# Sheet1.net
KiCad netlist of a schematic drawn in Altium Designer
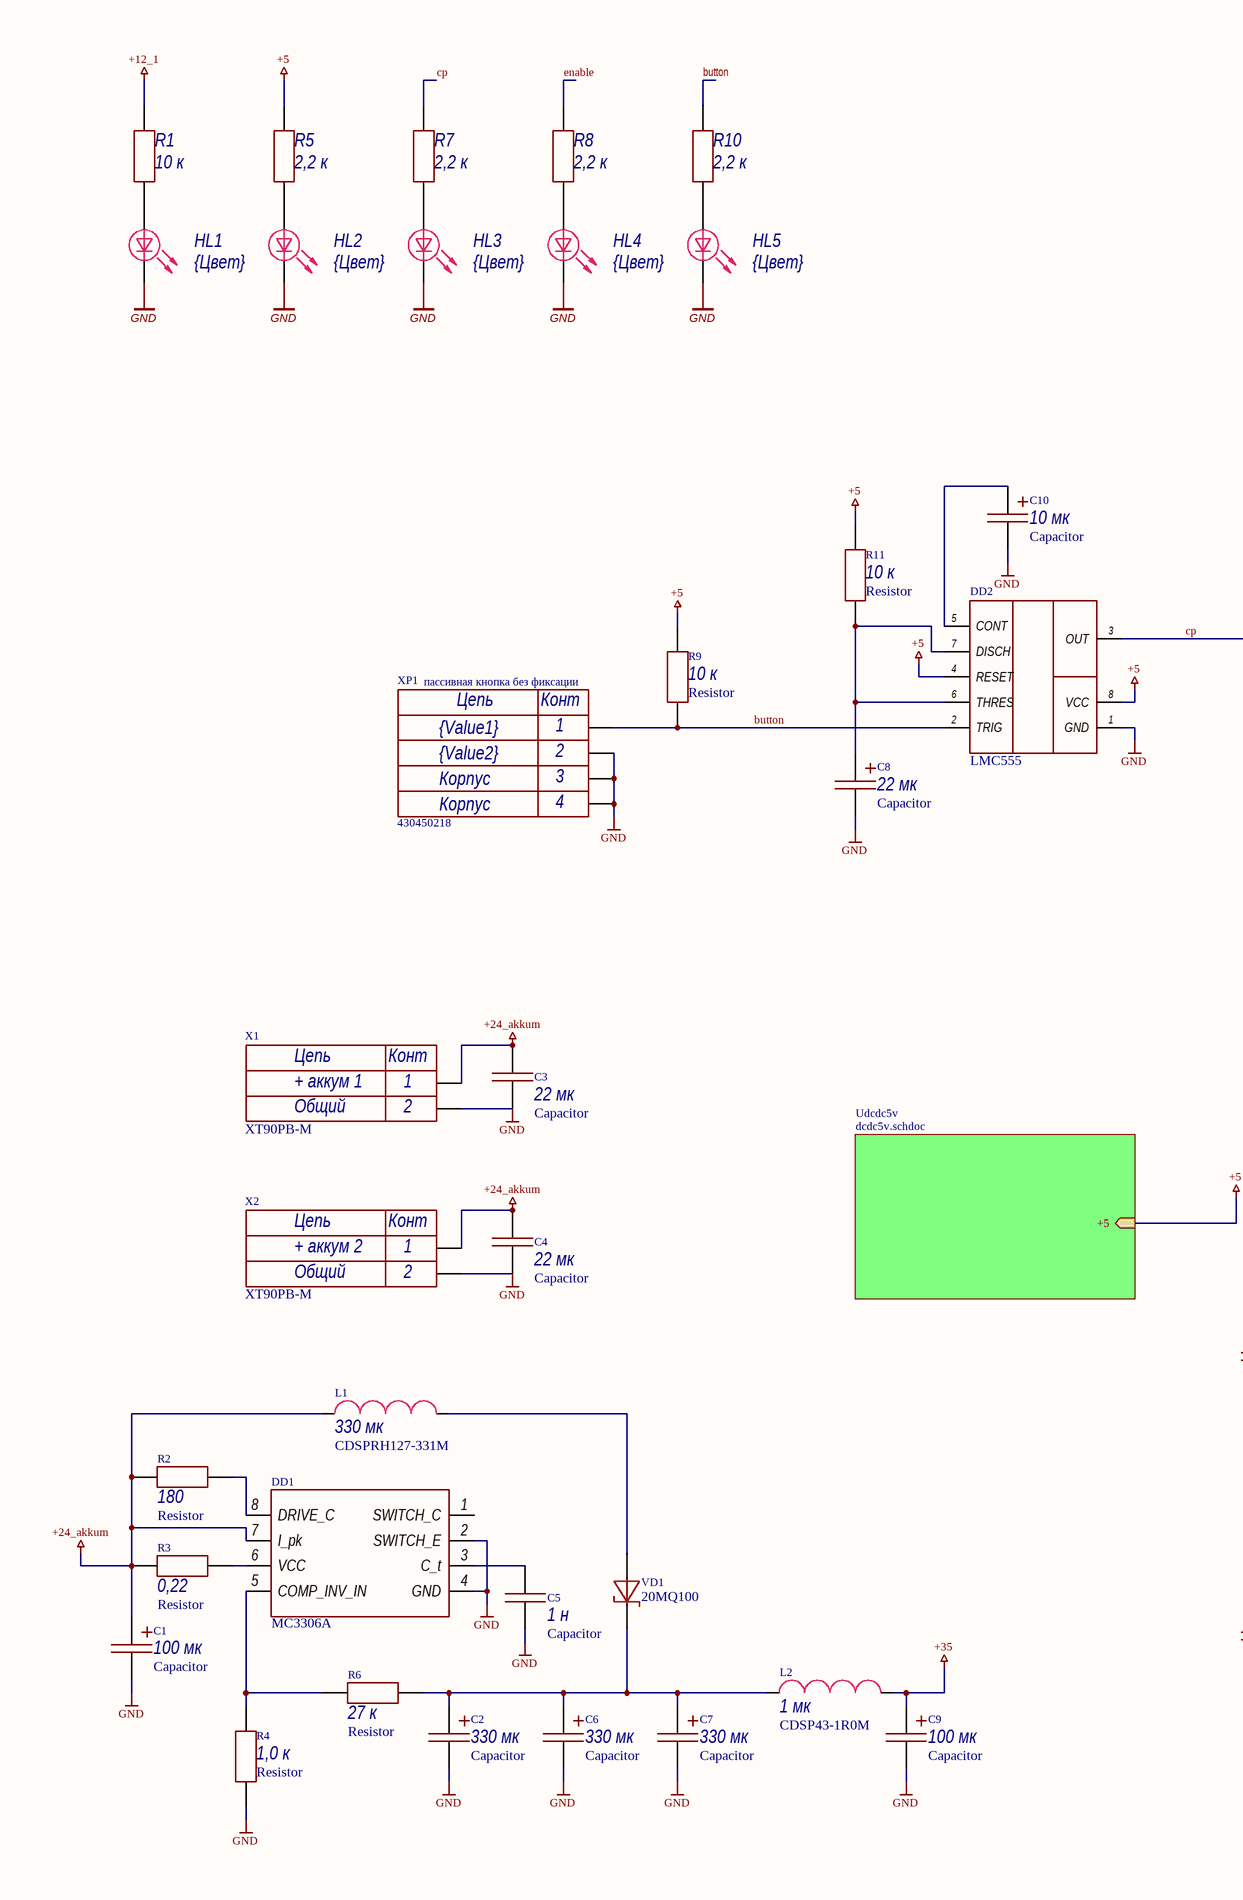
[diagram p0: Sheet1.SchDoc, left]
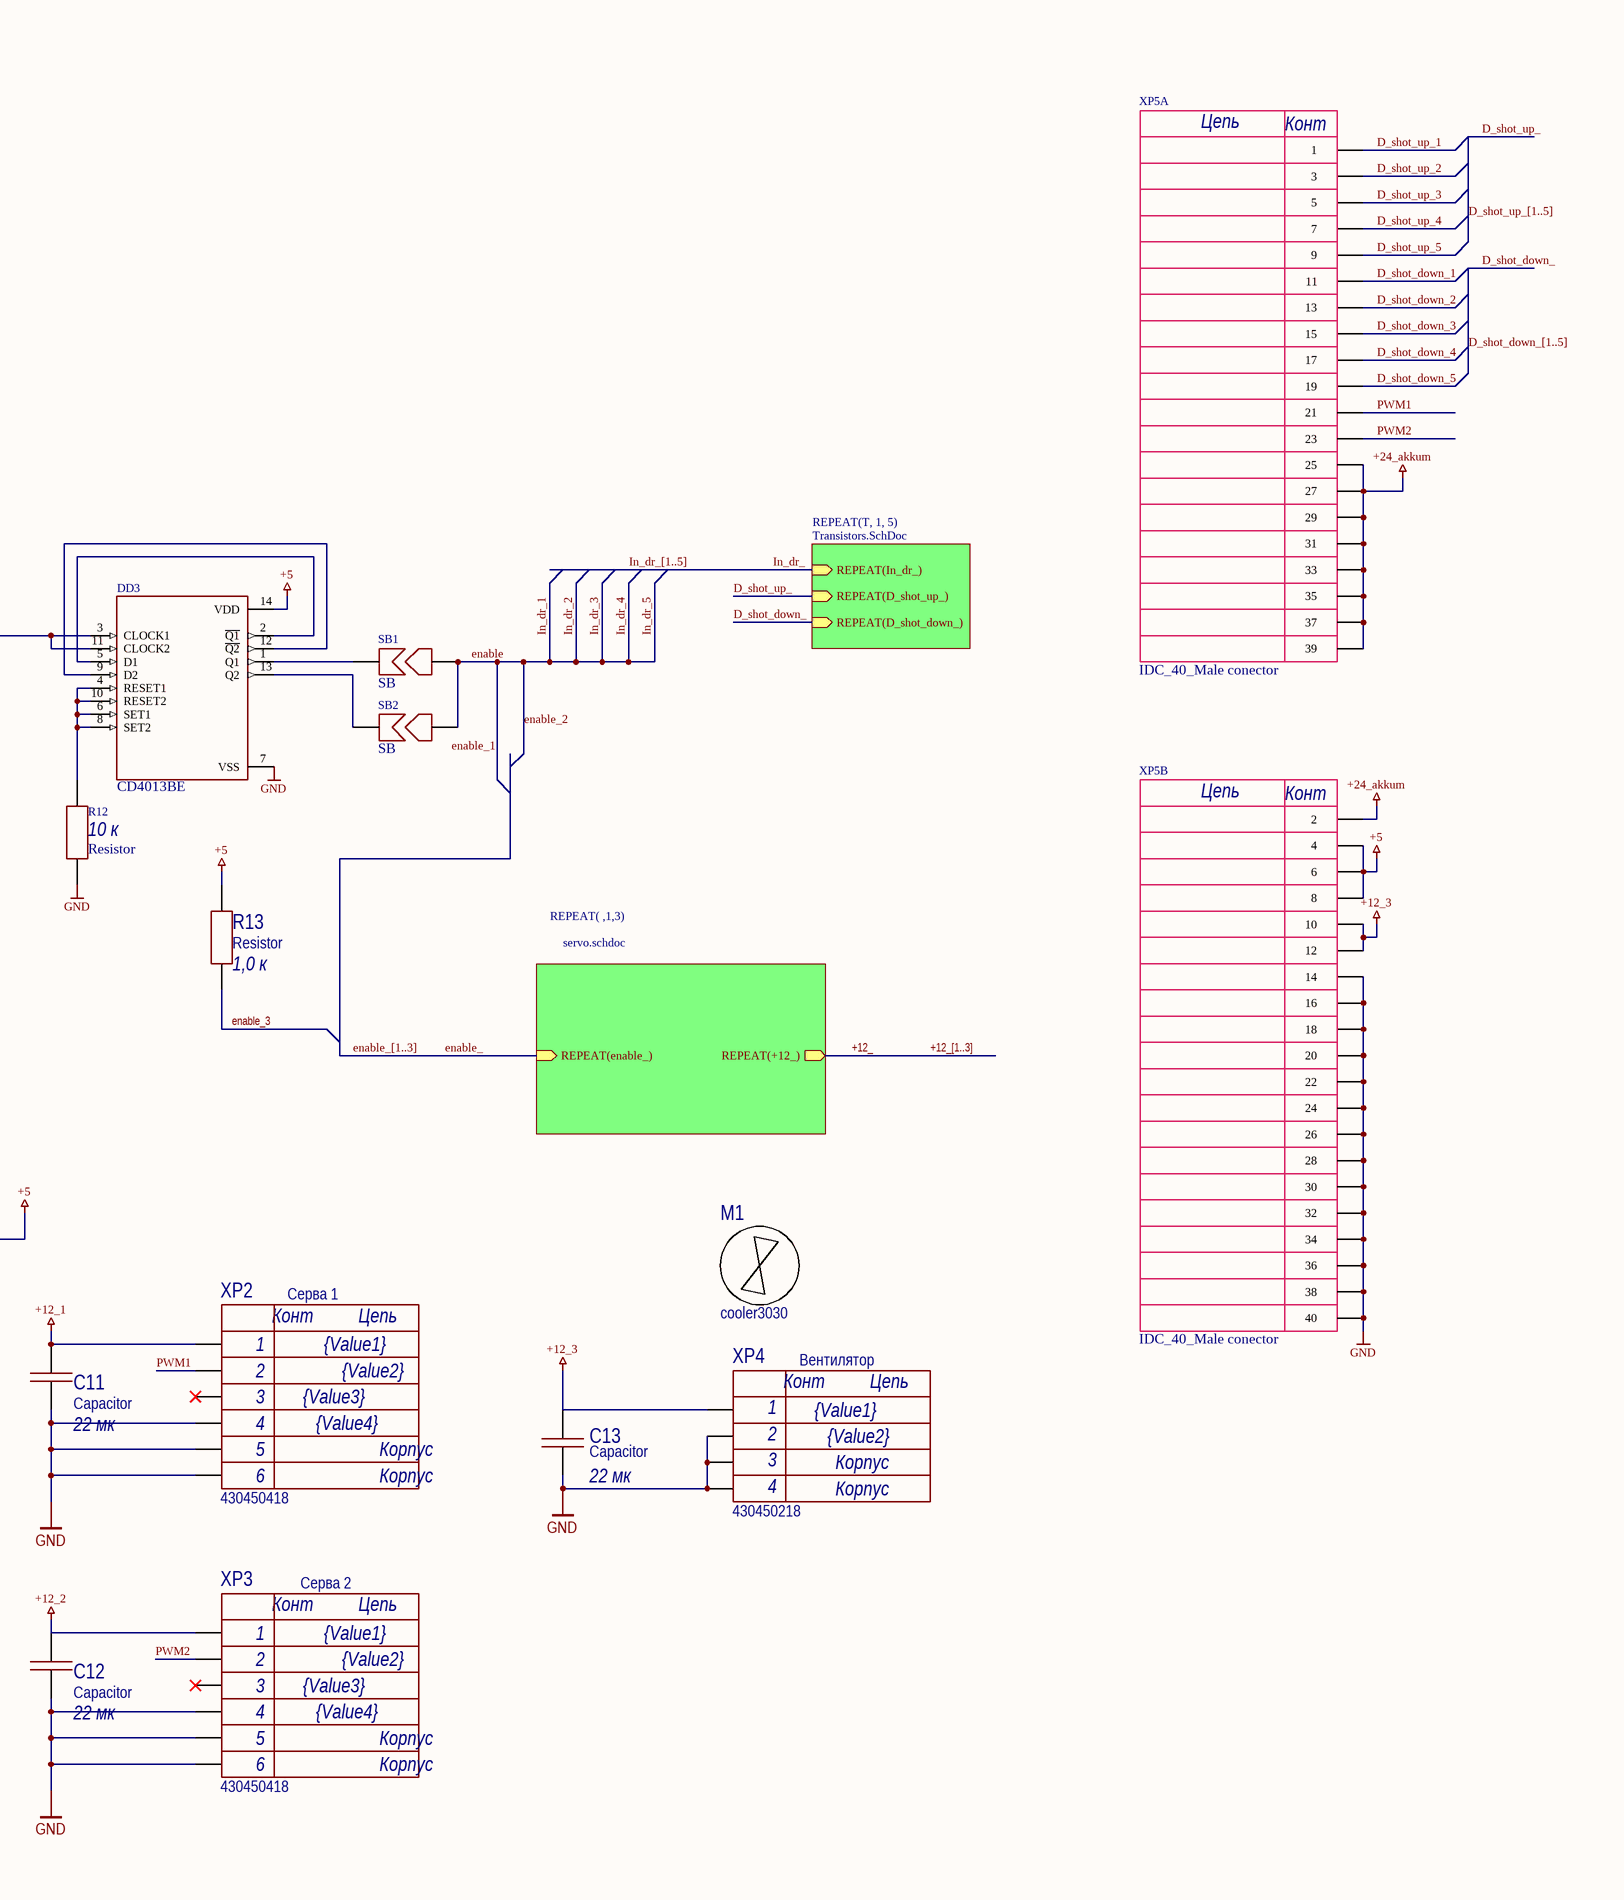
[diagram p1: Sheet1.SchDoc, right]

(export (version "E")
  (design (tool "Eeschema 10.0.6"))
  (components
    (comp (ref "C1")
      (value "Capacitor")
      (footprint "ECAP_SMD_6,6x6,6")
      (description "Конденсатор алюминиевый электролитический 100мкФ 35В 20% SMD 6,6x6,6 мм")
      (fields
        (field (name "ALTIUM_VALUE") "100 мк")
        (field (name "PART NUMBER") "JCK1V101")
        (field (name "TOLERANCE") "20")
      )
      (libsource (lib "Hydrolib") (part "Capacitor_polar"))
    )
    (comp (ref "C2")
      (value "Capacitor")
      (footprint "ECAP_SMD_10,3x10,3")
      (description "Конденсатор алюминиевый электролитический 1000мкФ 25В 20% Low ESR 1100мА SMD12.5x13.5мм")
      (fields
        (field (name "ALTIUM_VALUE") "330 мк")
        (field (name "PART NUMBER") "JCK1V331")
        (field (name "TOLERANCE") "20")
      )
      (libsource (lib "Hydrolib") (part "Capacitor_polar"))
    )
    (comp (ref "C3")
      (value "Capacitor")
      (footprint "1210C")
      (description "Конденсатор")
      (fields
        (field (name "ALTIUM_VALUE") "22 мк")
        (field (name "PART NUMBER") "Capacitor_22u_10_25V_X7R_1210C")
        (field (name "TOLERANCE") "0,1")
      )
      (libsource (lib "Hydrolib") (part "Capacitor"))
    )
    (comp (ref "C4")
      (value "Capacitor")
      (footprint "1210C")
      (description "Конденсатор")
      (fields
        (field (name "ALTIUM_VALUE") "22 мк")
        (field (name "PART NUMBER") "Capacitor_22u_10_25V_X7R_1210C")
        (field (name "TOLERANCE") "0,1")
      )
      (libsource (lib "Hydrolib") (part "Capacitor"))
    )
    (comp (ref "C5")
      (value "Capacitor")
      (footprint "0603C")
      (description "Конденсатор")
      (fields
        (field (name "ALTIUM_VALUE") "1 н")
        (field (name "PART NUMBER") "Capacitor_1n_10_50V_X7R_0603C")
        (field (name "TOLERANCE") "0,1")
      )
      (libsource (lib "Hydrolib") (part "Capacitor"))
    )
    (comp (ref "C6")
      (value "Capacitor")
      (footprint "ECAP_SMD_10,3x10,3")
      (description "Конденсатор алюминиевый электролитический 1000мкФ 25В 20% Low ESR 1100мА SMD12.5x13.5мм")
      (fields
        (field (name "ALTIUM_VALUE") "330 мк")
        (field (name "PART NUMBER") "JCK1V331")
        (field (name "TOLERANCE") "20")
      )
      (libsource (lib "Hydrolib") (part "Capacitor_polar"))
    )
    (comp (ref "C7")
      (value "Capacitor")
      (footprint "ECAP_SMD_10,3x10,3")
      (description "Конденсатор алюминиевый электролитический 1000мкФ 25В 20% Low ESR 1100мА SMD12.5x13.5мм")
      (fields
        (field (name "ALTIUM_VALUE") "330 мк")
        (field (name "PART NUMBER") "JCK1V331")
        (field (name "TOLERANCE") "20")
      )
      (libsource (lib "Hydrolib") (part "Capacitor_polar"))
    )
    (comp (ref "C8")
      (value "Capacitor")
      (footprint "TC_A")
      (description "Танталовый конденсатор")
      (fields
        (field (name "ALTIUM_VALUE") "22 мк")
        (field (name "PART NUMBER") "Capacitor_22u_10_50V_TC_A")
        (field (name "TOLERANCE") "0,1")
      )
      (libsource (lib "Hydrolib") (part "Capacitor_polar"))
    )
    (comp (ref "C9")
      (value "Capacitor")
      (footprint "ECAP_SMD_6,6x6,6")
      (description "Конденсатор алюминиевый электролитический 100мкФ 35В 20% SMD 6,6x6,6 мм")
      (fields
        (field (name "ALTIUM_VALUE") "100 мк")
        (field (name "PART NUMBER") "JCK1V101")
        (field (name "TOLERANCE") "20")
      )
      (libsource (lib "Hydrolib") (part "Capacitor_polar"))
    )
    (comp (ref "C10")
      (value "Capacitor")
      (footprint "TC_A")
      (description "Танталовый конденсатор")
      (fields
        (field (name "ALTIUM_VALUE") "10 мк")
        (field (name "PART NUMBER") "Capacitor_10u_10_50V_TC_A")
        (field (name "TOLERANCE") "0,1")
      )
      (libsource (lib "Hydrolib") (part "Capacitor_polar"))
    )
    (comp (ref "C11")
      (value "Capacitor")
      (footprint "1210C")
      (description "Конденсатор")
      (fields
        (field (name "ALTIUM_VALUE") "22 мк")
        (field (name "PART NUMBER") "Capacitor_22u_10_25V_X7R_1210C")
        (field (name "TOLERANCE") "0,1")
      )
      (libsource (lib "Hydrolib") (part "Capacitor"))
    )
    (comp (ref "C12")
      (value "Capacitor")
      (footprint "1210C")
      (description "Конденсатор")
      (fields
        (field (name "ALTIUM_VALUE") "22 мк")
        (field (name "PART NUMBER") "Capacitor_22u_10_25V_X7R_1210C")
        (field (name "TOLERANCE") "0,1")
      )
      (libsource (lib "Hydrolib") (part "Capacitor"))
    )
    (comp (ref "C13")
      (value "Capacitor")
      (footprint "1210C")
      (description "Конденсатор")
      (fields
        (field (name "ALTIUM_VALUE") "22 мк")
        (field (name "PART NUMBER") "Capacitor_22u_10_25V_X7R_1210C")
        (field (name "TOLERANCE") "0,1")
      )
      (libsource (lib "Hydrolib") (part "Capacitor"))
    )
    (comp (ref "DD1")
      (value "MC3306A")
      (footprint "SOIC-8")
      (description "DC-DC понижающий/повышающий преобразователь, вход: 3 - 40 В, выход: 1,25 - 40 В 1,5 А")
      (libsource (lib "Hydrolib") (part "MC3306A"))
    )
    (comp (ref "DD2")
      (value "LMC555")
      (footprint "SOIC-8")
      (description "Таймер интегральный прецизионный КМОП")
      (libsource (lib "Hydrolib") (part "NE555"))
    )
    (comp (ref "DD3")
      (value "CD4013BE")
      (footprint "DIP14_IN_SOCKET")
      (description "Два триггера D-типа")
      (libsource (lib "Hydrolib") (part "CD4013BE"))
    )
    (comp (ref "HL1")
      (value "LED")
      (footprint "0805D")
      (description "Светодиод")
      (fields (field (name "COLOR") "{Цвет}"))
      (libsource (lib "Hydrolib") (part "LED"))
    )
    (comp (ref "HL2")
      (value "LED")
      (footprint "0805D")
      (description "Светодиод")
      (fields (field (name "COLOR") "{Цвет}"))
      (libsource (lib "Hydrolib") (part "LED"))
    )
    (comp (ref "HL3")
      (value "LED")
      (footprint "0805D")
      (description "Светодиод")
      (fields (field (name "COLOR") "{Цвет}"))
      (libsource (lib "Hydrolib") (part "LED"))
    )
    (comp (ref "HL4")
      (value "LED")
      (footprint "0805D")
      (description "Светодиод")
      (fields (field (name "COLOR") "{Цвет}"))
      (libsource (lib "Hydrolib") (part "LED"))
    )
    (comp (ref "HL5")
      (value "LED")
      (footprint "0805D")
      (description "Светодиод")
      (fields (field (name "COLOR") "{Цвет}"))
      (libsource (lib "Hydrolib") (part "LED"))
    )
    (comp (ref "L1")
      (value "CDSPRH127-331M")
      (footprint "12.8x12.8")
      (description "Индуктивность на 330 мкГн, номинальный ток 1,79 A")
      (fields (field (name "ALTIUM_VALUE") "330 мк"))
      (libsource (lib "Hydrolib") (part "Inductance"))
    )
    (comp (ref "L2")
      (value "CDSP43-1R0M")
      (footprint "4.5x4_wired")
      (description "Индуктивность на 1 мкГн, номинальный ток 4,3 A")
      (fields (field (name "ALTIUM_VALUE") "1 мк"))
      (libsource (lib "Hydrolib") (part "Inductance"))
    )
    (comp (ref "M1")
      (value "cooler3030")
      (footprint "cooler3030")
      (description "вентилятор 30*30 с дыркой на плате")
      (libsource (lib "Hydrolib") (part "cooler4040"))
    )
    (comp (ref "R1")
      (value "10 к")
      (footprint "0603R")
      (description "Резистор номиналом 10 кОм и точностью 1%")
      (fields (field (name "PART NUMBER") "Resistor_10k_1_0603") (field (name "TOLERANCE") "1%"))
      (libsource (lib "Hydrolib") (part "Resistor"))
    )
    (comp (ref "R2")
      (value "Resistor")
      (footprint "0603R")
      (description "Резистор номиналом 180 Ом и точностью 1%")
      (fields
        (field (name "ALTIUM_VALUE") "180")
        (field (name "PART NUMBER") "Resistor_180_1_0603")
        (field (name "TOLERANCE") "1%")
      )
      (libsource (lib "") (part "Resistor_1"))
    )
    (comp (ref "R3")
      (value "Resistor")
      (footprint "2512R")
      (description "Резистор номиналом 0,22 Ом и точностью 1%")
      (fields
        (field (name "ALTIUM_VALUE") "0,22")
        (field (name "PART NUMBER") "Resistor_0.22_1_2512")
        (field (name "TOLERANCE") "1%")
      )
      (libsource (lib "") (part "Resistor_1"))
    )
    (comp (ref "R4")
      (value "Resistor")
      (footprint "0603R")
      (description "Резистор номиналом 1,0 кОм и точностью 1%")
      (fields
        (field (name "ALTIUM_VALUE") "1,0 к")
        (field (name "PART NUMBER") "Resistor_1.0k_1_0603")
        (field (name "TOLERANCE") "1%")
      )
      (libsource (lib "Hydrolib") (part "Resistor"))
    )
    (comp (ref "R5")
      (value "2,2 к")
      (footprint "0603R")
      (description "Резистор номиналом 2,2 кОм и точностью 1%")
      (fields (field (name "PART NUMBER") "Resistor_2.2k_1_0603") (field (name "TOLERANCE") "1%"))
      (libsource (lib "Hydrolib") (part "Resistor"))
    )
    (comp (ref "R6")
      (value "Resistor")
      (footprint "0603R")
      (description "Резистор номиналом 27 кОм и точностью 1%")
      (fields
        (field (name "ALTIUM_VALUE") "27 к")
        (field (name "PART NUMBER") "Resistor_27k_1_0603")
        (field (name "TOLERANCE") "1%")
      )
      (libsource (lib "") (part "Resistor_2"))
    )
    (comp (ref "R7")
      (value "2,2 к")
      (footprint "0603R")
      (description "Резистор номиналом 2,2 кОм и точностью 1%")
      (fields (field (name "PART NUMBER") "Resistor_2.2k_1_0603") (field (name "TOLERANCE") "1%"))
      (libsource (lib "Hydrolib") (part "Resistor"))
    )
    (comp (ref "R8")
      (value "2,2 к")
      (footprint "0603R")
      (description "Резистор номиналом 2,2 кОм и точностью 1%")
      (fields (field (name "PART NUMBER") "Resistor_2.2k_1_0603") (field (name "TOLERANCE") "1%"))
      (libsource (lib "Hydrolib") (part "Resistor"))
    )
    (comp (ref "R9")
      (value "Resistor")
      (footprint "0603R")
      (description "Резистор номиналом 10 кОм и точностью 1%")
      (fields
        (field (name "ALTIUM_VALUE") "10 к")
        (field (name "PART NUMBER") "Resistor_10k_1_0603")
        (field (name "TOLERANCE") "1%")
      )
      (libsource (lib "Hydrolib") (part "Resistor"))
    )
    (comp (ref "R10")
      (value "2,2 к")
      (footprint "0603R")
      (description "Резистор номиналом 2,2 кОм и точностью 1%")
      (fields (field (name "PART NUMBER") "Resistor_2.2k_1_0603") (field (name "TOLERANCE") "1%"))
      (libsource (lib "Hydrolib") (part "Resistor"))
    )
    (comp (ref "R11")
      (value "Resistor")
      (footprint "0603R")
      (description "Резистор номиналом 10 кОм и точностью 1%")
      (fields
        (field (name "ALTIUM_VALUE") "10 к")
        (field (name "PART NUMBER") "Resistor_10k_1_0603")
        (field (name "TOLERANCE") "1%")
      )
      (libsource (lib "Hydrolib") (part "Resistor"))
    )
    (comp (ref "R12")
      (value "Resistor")
      (footprint "0603R")
      (description "Резистор номиналом 10 кОм и точностью 1%")
      (fields
        (field (name "ALTIUM_VALUE") "10 к")
        (field (name "PART NUMBER") "Resistor_10k_1_0603")
        (field (name "TOLERANCE") "1%")
      )
      (libsource (lib "Hydrolib") (part "Resistor"))
    )
    (comp (ref "R13")
      (value "Resistor")
      (footprint "0603R")
      (description "Резистор номиналом 1,0 кОм и точностью 1%")
      (fields
        (field (name "ALTIUM_VALUE") "1,0 к")
        (field (name "PART NUMBER") "Resistor_1.0k_1_0603")
        (field (name "TOLERANCE") "1%")
      )
      (libsource (lib "Hydrolib") (part "Resistor"))
    )
    (comp (ref "SB1")
      (value "SB")
      (footprint "0805SB")
      (description "Solder bridge, мост припоя, запаиваемая перемычка, net tie, jumper")
      (libsource (lib "Hydrolib") (part "SB"))
    )
    (comp (ref "SB2")
      (value "SB")
      (footprint "0805SB")
      (description "Solder bridge, мост припоя, запаиваемая перемычка, net tie, jumper")
      (libsource (lib "Hydrolib") (part "SB"))
    )
    (comp (ref "VD1")
      (value "20MQ100")
      (footprint "SMA")
      (description "Диод шоттки на 100 В, ном. ток 2 А")
      (libsource (lib "Hydrolib") (part "Schottky_diode"))
    )
    (comp (ref "X1")
      (value "XT90PB-M")
      (footprint "XT90PB-M")
      (description "90 А (60 продолжительно), 2 контакта, прямой отец")
      (fields (field (name "VALUE2") "Общий") (field (name "VALUE1") "+ аккум 1"))
      (libsource (lib "Hydrolib") (part "Polar_Conn"))
    )
    (comp (ref "X2")
      (value "XT90PB-M")
      (footprint "XT90PB-M")
      (description "90 А (60 продолжительно), 2 контакта, прямой отец")
      (fields (field (name "VALUE2") "Общий") (field (name "VALUE1") "+ аккум 2"))
      (libsource (lib "Hydrolib") (part "Polar_Conn"))
    )
    (comp (ref "XP1")
      (value "430450218")
      (footprint "Molex_430450218")
      (fields
        (field (name "VALUE3") "Корпус")
        (field (name "VALUE2") "{Value2}")
        (field (name "VALUE4") "Корпус")
        (field (name "VALUE1") "{Value1}")
        (field (name "PART NUMBER") "Molex_430450218")
      )
      (libsource (lib "Hydrolib") (part "Molex_430450218"))
    )
    (comp (ref "XP2")
      (value "430450418")
      (footprint "MOLEX_430450418")
      (description "Разъем типа провод-плата, 3 мм, 4 контакт(-ов), Штыревой Разъем, для поверностного монтажа")
      (fields
        (field (name "VALUE1") "{Value1}")
        (field (name "VALUE2") "{Value2}")
        (field (name "VALUE3") "{Value3}")
        (field (name "VALUE4") "{Value4}")
        (field (name "PART NUMBER") "Molex_430450418")
      )
      (libsource (lib "Hydrolib") (part "Molex_430450415"))
    )
    (comp (ref "XP3")
      (value "430450418")
      (footprint "MOLEX_430450418")
      (description "Разъем типа провод-плата, 3 мм, 4 контакт(-ов), Штыревой Разъем, для поверностного монтажа")
      (fields
        (field (name "VALUE1") "{Value1}")
        (field (name "VALUE2") "{Value2}")
        (field (name "VALUE3") "{Value3}")
        (field (name "VALUE4") "{Value4}")
        (field (name "PART NUMBER") "Molex_430450418")
      )
      (libsource (lib "Hydrolib") (part "Molex_430450415"))
    )
    (comp (ref "XP4")
      (value "430450218")
      (footprint "Molex_430450218")
      (fields
        (field (name "VALUE3") "Корпус")
        (field (name "VALUE2") "{Value2}")
        (field (name "VALUE4") "Корпус")
        (field (name "VALUE1") "{Value1}")
        (field (name "PART NUMBER") "Molex_430450218")
      )
      (libsource (lib "Hydrolib") (part "Molex_430450218"))
    )
    (comp (ref "XP5")
      (value "IDC_40_Male conector")
      (footprint "IDC_40_Male conector")
      (description "IDC 40-пиновый разъём прямая вилка")
      (libsource (lib "Hydrolib") (part "Conn_40pin"))
    )
  )
  (nets
    (net (code "1") (name "+5") (class "Default")
      (node (ref "DD2") (pin "4") (pinfunction "RESET_4") (pintype "passive"))
      (node (ref "DD2") (pin "8") (pinfunction "VCC_8") (pintype "passive"))
      (node (ref "DD3") (pin "14") (pinfunction "VDD_14") (pintype "power_in"))
      (node (ref "R11") (pin "2") (pinfunction "2_2") (pintype "passive"))
      (node (ref "R13") (pin "2") (pinfunction "2_2") (pintype "passive"))
      (node (ref "R5") (pin "2") (pinfunction "2_2") (pintype "passive"))
      (node (ref "R9") (pin "2") (pinfunction "2_2") (pintype "passive"))
      (node (ref "XP5") (pin "4") (pinfunction "4_4") (pintype "passive"))
      (node (ref "XP5") (pin "6") (pinfunction "6_6") (pintype "passive"))
      (node (ref "XP5") (pin "8") (pinfunction "8_8") (pintype "passive"))
    )
    (net (code "2") (name "+12_1") (class "Default")
      (node (ref "C11") (pin "2") (pinfunction "2_2") (pintype "passive"))
      (node (ref "R1") (pin "2") (pinfunction "2_2") (pintype "passive"))
      (node (ref "XP2") (pin "1") (pinfunction "1_1") (pintype "passive"))
    )
    (net (code "3") (name "+12_2") (class "Default")
      (node (ref "C12") (pin "2") (pinfunction "2_2") (pintype "passive"))
      (node (ref "XP3") (pin "1") (pinfunction "1_1") (pintype "passive"))
    )
    (net (code "4") (name "+12_3") (class "Default")
      (node (ref "C13") (pin "2") (pinfunction "2_2") (pintype "passive"))
      (node (ref "XP4") (pin "1") (pinfunction "1_1") (pintype "passive"))
      (node (ref "XP5") (pin "10") (pinfunction "10_10") (pintype "passive"))
      (node (ref "XP5") (pin "12") (pinfunction "12_12") (pintype "passive"))
    )
    (net (code "5") (name "+24_akkum") (class "Default")
      (node (ref "C1") (pin "1") (pinfunction "1_1") (pintype "passive"))
      (node (ref "C3") (pin "2") (pinfunction "2_2") (pintype "passive"))
      (node (ref "C4") (pin "2") (pinfunction "2_2") (pintype "passive"))
      (node (ref "DD1") (pin "7") (pinfunction "I_pk_7") (pintype "passive"))
      (node (ref "L1") (pin "1") (pinfunction "1_1") (pintype "passive"))
      (node (ref "R2") (pin "2") (pinfunction "2_2") (pintype "passive"))
      (node (ref "R3") (pin "2") (pinfunction "2_2") (pintype "passive"))
      (node (ref "X1") (pin "P") (pinfunction "P_P") (pintype "passive"))
      (node (ref "X2") (pin "P") (pinfunction "P_P") (pintype "passive"))
      (node (ref "XP5") (pin "2") (pinfunction "2_2") (pintype "passive"))
      (node (ref "XP5") (pin "25") (pinfunction "25_25") (pintype "passive"))
      (node (ref "XP5") (pin "27") (pinfunction "27_27") (pintype "passive"))
      (node (ref "XP5") (pin "29") (pinfunction "29_29") (pintype "passive"))
      (node (ref "XP5") (pin "31") (pinfunction "31_31") (pintype "passive"))
      (node (ref "XP5") (pin "33") (pinfunction "33_33") (pintype "passive"))
      (node (ref "XP5") (pin "35") (pinfunction "35_35") (pintype "passive"))
      (node (ref "XP5") (pin "37") (pinfunction "37_37") (pintype "passive"))
      (node (ref "XP5") (pin "39") (pinfunction "39_39") (pintype "passive"))
    )
    (net (code "6") (name "+35") (class "Default")
      (node (ref "C9") (pin "1") (pinfunction "1_1") (pintype "passive"))
      (node (ref "L2") (pin "2") (pinfunction "2_2") (pintype "passive"))
    )
    (net (code "10") (name "/D_shot_down_1") (class "Default")
      (node (ref "XP5") (pin "11") (pinfunction "11_11") (pintype "passive"))
    )
    (net (code "11") (name "/D_shot_down_2") (class "Default")
      (node (ref "XP5") (pin "13") (pinfunction "13_13") (pintype "passive"))
    )
    (net (code "12") (name "/D_shot_down_3") (class "Default")
      (node (ref "XP5") (pin "15") (pinfunction "15_15") (pintype "passive"))
    )
    (net (code "13") (name "/D_shot_down_4") (class "Default")
      (node (ref "XP5") (pin "17") (pinfunction "17_17") (pintype "passive"))
    )
    (net (code "14") (name "/D_shot_down_5") (class "Default")
      (node (ref "XP5") (pin "19") (pinfunction "19_19") (pintype "passive"))
    )
    (net (code "17") (name "/D_shot_up_1") (class "Default")
      (node (ref "XP5") (pin "1") (pinfunction "1_1") (pintype "passive"))
    )
    (net (code "18") (name "/D_shot_up_2") (class "Default")
      (node (ref "XP5") (pin "3") (pinfunction "3_3") (pintype "passive"))
    )
    (net (code "19") (name "/D_shot_up_3") (class "Default")
      (node (ref "XP5") (pin "5") (pinfunction "5_5") (pintype "passive"))
    )
    (net (code "20") (name "/D_shot_up_4") (class "Default")
      (node (ref "XP5") (pin "7") (pinfunction "7_7") (pintype "passive"))
    )
    (net (code "21") (name "/D_shot_up_5") (class "Default")
      (node (ref "XP5") (pin "9") (pinfunction "9_9") (pintype "passive"))
    )
    (net (code "25") (name "/PWM1") (class "Default")
      (node (ref "XP2") (pin "2") (pinfunction "2_2") (pintype "passive"))
      (node (ref "XP5") (pin "21") (pinfunction "21_21") (pintype "passive"))
    )
    (net (code "26") (name "/PWM2") (class "Default")
      (node (ref "XP3") (pin "2") (pinfunction "2_2") (pintype "passive"))
      (node (ref "XP5") (pin "23") (pinfunction "23_23") (pintype "passive"))
    )
    (net (code "27") (name "/button") (class "Default")
      (node (ref "DD2") (pin "2") (pinfunction "TRIG_2") (pintype "passive"))
      (node (ref "R10") (pin "2") (pinfunction "2_2") (pintype "passive"))
      (node (ref "R9") (pin "1") (pinfunction "1_1") (pintype "passive"))
      (node (ref "XP1") (pin "1") (pinfunction "1_1") (pintype "passive"))
    )
    (net (code "28") (name "/cp") (class "Default")
      (node (ref "DD2") (pin "3") (pinfunction "OUT_3") (pintype "passive"))
      (node (ref "DD3") (pin "11") (pinfunction "CLOCK2_11") (pintype "input"))
      (node (ref "DD3") (pin "3") (pinfunction "CLOCK1_3") (pintype "input"))
      (node (ref "R7") (pin "2") (pinfunction "2_2") (pintype "passive"))
    )
    (net (code "30") (name "/enable_2") (class "Default")
      (node (ref "R8") (pin "2") (pinfunction "2_2") (pintype "passive"))
      (node (ref "SB1") (pin "1") (pinfunction "1_1") (pintype "passive"))
      (node (ref "SB2") (pin "1") (pinfunction "1_1") (pintype "passive"))
    )
    (net (code "31") (name "/enable_3") (class "Default")
      (node (ref "R13") (pin "1") (pinfunction "1_1") (pintype "passive"))
    )
    (net (code "33") (name "GND") (class "Default")
      (node (ref "C1") (pin "2") (pinfunction "2_2") (pintype "passive"))
      (node (ref "C10") (pin "2") (pinfunction "2_2") (pintype "passive"))
      (node (ref "C11") (pin "1") (pinfunction "1_1") (pintype "passive"))
      (node (ref "C12") (pin "1") (pinfunction "1_1") (pintype "passive"))
      (node (ref "C13") (pin "1") (pinfunction "1_1") (pintype "passive"))
      (node (ref "C2") (pin "2") (pinfunction "2_2") (pintype "passive"))
      (node (ref "C3") (pin "1") (pinfunction "1_1") (pintype "passive"))
      (node (ref "C4") (pin "1") (pinfunction "1_1") (pintype "passive"))
      (node (ref "C5") (pin "2") (pinfunction "2_2") (pintype "passive"))
      (node (ref "C6") (pin "2") (pinfunction "2_2") (pintype "passive"))
      (node (ref "C7") (pin "2") (pinfunction "2_2") (pintype "passive"))
      (node (ref "C8") (pin "2") (pinfunction "2_2") (pintype "passive"))
      (node (ref "C9") (pin "2") (pinfunction "2_2") (pintype "passive"))
      (node (ref "DD1") (pin "2") (pinfunction "SWITCH_E_2") (pintype "passive"))
      (node (ref "DD1") (pin "4") (pinfunction "GND_4") (pintype "passive"))
      (node (ref "DD2") (pin "1") (pinfunction "GND_1") (pintype "passive"))
      (node (ref "DD3") (pin "7") (pinfunction "VSS_7") (pintype "power_in"))
      (node (ref "HL1") (pin "2") (pinfunction "2_2") (pintype "passive"))
      (node (ref "HL2") (pin "2") (pinfunction "2_2") (pintype "passive"))
      (node (ref "HL3") (pin "2") (pinfunction "2_2") (pintype "passive"))
      (node (ref "HL4") (pin "2") (pinfunction "2_2") (pintype "passive"))
      (node (ref "HL5") (pin "2") (pinfunction "2_2") (pintype "passive"))
      (node (ref "R12") (pin "1") (pinfunction "1_1") (pintype "passive"))
      (node (ref "R4") (pin "1") (pinfunction "1_1") (pintype "passive"))
      (node (ref "X1") (pin "N") (pinfunction "N_N") (pintype "passive"))
      (node (ref "X2") (pin "N") (pinfunction "N_N") (pintype "passive"))
      (node (ref "XP1") (pin "0") (pinfunction "0_0") (pintype "passive"))
      (node (ref "XP1") (pin "2") (pinfunction "2_2") (pintype "passive"))
      (node (ref "XP2") (pin "0") (pinfunction "0_0") (pintype "passive"))
      (node (ref "XP2") (pin "4") (pinfunction "4_4") (pintype "passive"))
      (node (ref "XP3") (pin "0") (pinfunction "0_0") (pintype "passive"))
      (node (ref "XP3") (pin "4") (pinfunction "4_4") (pintype "passive"))
      (node (ref "XP4") (pin "0") (pinfunction "0_0") (pintype "passive"))
      (node (ref "XP4") (pin "2") (pinfunction "2_2") (pintype "passive"))
      (node (ref "XP5") (pin "14") (pinfunction "14_14") (pintype "passive"))
      (node (ref "XP5") (pin "16") (pinfunction "16_16") (pintype "passive"))
      (node (ref "XP5") (pin "18") (pinfunction "18_18") (pintype "passive"))
      (node (ref "XP5") (pin "20") (pinfunction "20_20") (pintype "passive"))
      (node (ref "XP5") (pin "22") (pinfunction "22_22") (pintype "passive"))
      (node (ref "XP5") (pin "24") (pinfunction "24_24") (pintype "passive"))
      (node (ref "XP5") (pin "26") (pinfunction "26_26") (pintype "passive"))
      (node (ref "XP5") (pin "28") (pinfunction "28_28") (pintype "passive"))
      (node (ref "XP5") (pin "30") (pinfunction "30_30") (pintype "passive"))
      (node (ref "XP5") (pin "32") (pinfunction "32_32") (pintype "passive"))
      (node (ref "XP5") (pin "34") (pinfunction "34_34") (pintype "passive"))
      (node (ref "XP5") (pin "36") (pinfunction "36_36") (pintype "passive"))
      (node (ref "XP5") (pin "38") (pinfunction "38_38") (pintype "passive"))
      (node (ref "XP5") (pin "40") (pinfunction "40_40") (pintype "passive"))
    )
    (net (code "34") (name "Net-(C2-Pad1)") (class "Default")
      (node (ref "C2") (pin "1") (pinfunction "1_1") (pintype "passive"))
      (node (ref "C6") (pin "1") (pinfunction "1_1") (pintype "passive"))
      (node (ref "C7") (pin "1") (pinfunction "1_1") (pintype "passive"))
      (node (ref "L2") (pin "1") (pinfunction "1_1") (pintype "passive"))
      (node (ref "R6") (pin "2") (pinfunction "2_2") (pintype "passive"))
      (node (ref "VD1") (pin "2") (pinfunction "2_2") (pintype "passive"))
    )
    (net (code "35") (name "Net-(DD1-COMP_INV_IN)") (class "Default")
      (node (ref "DD1") (pin "5") (pinfunction "COMP_INV_IN_5") (pintype "passive"))
      (node (ref "R4") (pin "2") (pinfunction "2_2") (pintype "passive"))
      (node (ref "R6") (pin "1") (pinfunction "1_1") (pintype "passive"))
    )
    (net (code "36") (name "Net-(DD1-C_t)") (class "Default")
      (node (ref "C5") (pin "1") (pinfunction "1_1") (pintype "passive"))
      (node (ref "DD1") (pin "3") (pinfunction "C_t_3") (pintype "passive"))
    )
    (net (code "37") (name "Net-(DD1-DRIVE_C)") (class "Default")
      (node (ref "DD1") (pin "8") (pinfunction "DRIVE_C_8") (pintype "passive"))
      (node (ref "R2") (pin "1") (pinfunction "1_1") (pintype "passive"))
    )
    (net (code "38") (name "Net-(DD1-VCC)") (class "Default")
      (node (ref "DD1") (pin "6") (pinfunction "VCC_6") (pintype "passive"))
      (node (ref "R3") (pin "1") (pinfunction "1_1") (pintype "passive"))
    )
    (net (code "39") (name "Net-(DD2-CONT)") (class "Default")
      (node (ref "C10") (pin "1") (pinfunction "1_1") (pintype "passive"))
      (node (ref "DD2") (pin "5") (pinfunction "CONT_5") (pintype "passive"))
    )
    (net (code "40") (name "Net-(DD2-DISCH)") (class "Default")
      (node (ref "C8") (pin "1") (pinfunction "1_1") (pintype "passive"))
      (node (ref "DD2") (pin "6") (pinfunction "THRES_6") (pintype "passive"))
      (node (ref "DD2") (pin "7") (pinfunction "DISCH_7") (pintype "passive"))
      (node (ref "R11") (pin "1") (pinfunction "1_1") (pintype "passive"))
    )
    (net (code "41") (name "Net-(DD3-D1)") (class "Default")
      (node (ref "DD3") (pin "2") (pinfunction "~{Q1}_2") (pintype "output"))
      (node (ref "DD3") (pin "5") (pinfunction "D1_5") (pintype "input"))
    )
    (net (code "42") (name "Net-(DD3-D2)") (class "Default")
      (node (ref "DD3") (pin "12") (pinfunction "~{Q2}_12") (pintype "output"))
      (node (ref "DD3") (pin "9") (pinfunction "D2_9") (pintype "input"))
    )
    (net (code "43") (name "Net-(DD3-Q1)") (class "Default")
      (node (ref "DD3") (pin "1") (pinfunction "Q1_1") (pintype "output"))
      (node (ref "SB1") (pin "2") (pinfunction "2_2") (pintype "passive"))
    )
    (net (code "44") (name "Net-(DD3-Q2)") (class "Default")
      (node (ref "DD3") (pin "13") (pinfunction "Q2_13") (pintype "output"))
      (node (ref "SB2") (pin "2") (pinfunction "2_2") (pintype "passive"))
    )
    (net (code "45") (name "Net-(DD3-RESET1)") (class "Default")
      (node (ref "DD3") (pin "10") (pinfunction "RESET2_10") (pintype "input"))
      (node (ref "DD3") (pin "4") (pinfunction "RESET1_4") (pintype "input"))
      (node (ref "DD3") (pin "6") (pinfunction "SET1_6") (pintype "input"))
      (node (ref "DD3") (pin "8") (pinfunction "SET2_8") (pintype "input"))
      (node (ref "R12") (pin "2") (pinfunction "2_2") (pintype "passive"))
    )
    (net (code "46") (name "Net-(HL1-Pad1)") (class "Default")
      (node (ref "HL1") (pin "1") (pinfunction "1_1") (pintype "passive"))
      (node (ref "R1") (pin "1") (pinfunction "1_1") (pintype "passive"))
    )
    (net (code "47") (name "Net-(HL2-Pad1)") (class "Default")
      (node (ref "HL2") (pin "1") (pinfunction "1_1") (pintype "passive"))
      (node (ref "R5") (pin "1") (pinfunction "1_1") (pintype "passive"))
    )
    (net (code "48") (name "Net-(HL3-Pad1)") (class "Default")
      (node (ref "HL3") (pin "1") (pinfunction "1_1") (pintype "passive"))
      (node (ref "R7") (pin "1") (pinfunction "1_1") (pintype "passive"))
    )
    (net (code "49") (name "Net-(HL4-Pad1)") (class "Default")
      (node (ref "HL4") (pin "1") (pinfunction "1_1") (pintype "passive"))
      (node (ref "R8") (pin "1") (pinfunction "1_1") (pintype "passive"))
    )
    (net (code "50") (name "Net-(HL5-Pad1)") (class "Default")
      (node (ref "HL5") (pin "1") (pinfunction "1_1") (pintype "passive"))
      (node (ref "R10") (pin "1") (pinfunction "1_1") (pintype "passive"))
    )
    (net (code "51") (name "Net-(L1-Pad2)") (class "Default")
      (node (ref "L1") (pin "2") (pinfunction "2_2") (pintype "passive"))
      (node (ref "VD1") (pin "1") (pinfunction "1_1") (pintype "passive"))
    )
    (net (code "52") (name "unconnected-(DD1-SWITCH_C-Pad1)") (class "Default")
      (node (ref "DD1") (pin "1") (pinfunction "SWITCH_C_1") (pintype "passive"))
    )
    (net (code "53") (name "unconnected-(XP2-Pad3)") (class "Default")
      (node (ref "XP2") (pin "3") (pinfunction "3_3") (pintype "passive+no_connect"))
    )
    (net (code "54") (name "unconnected-(XP3-Pad3)") (class "Default")
      (node (ref "XP3") (pin "3") (pinfunction "3_3") (pintype "passive+no_connect"))
    )
  )
)
